# nautilus-board.net
KiCad netlist of a schematic drawn in EAGLE
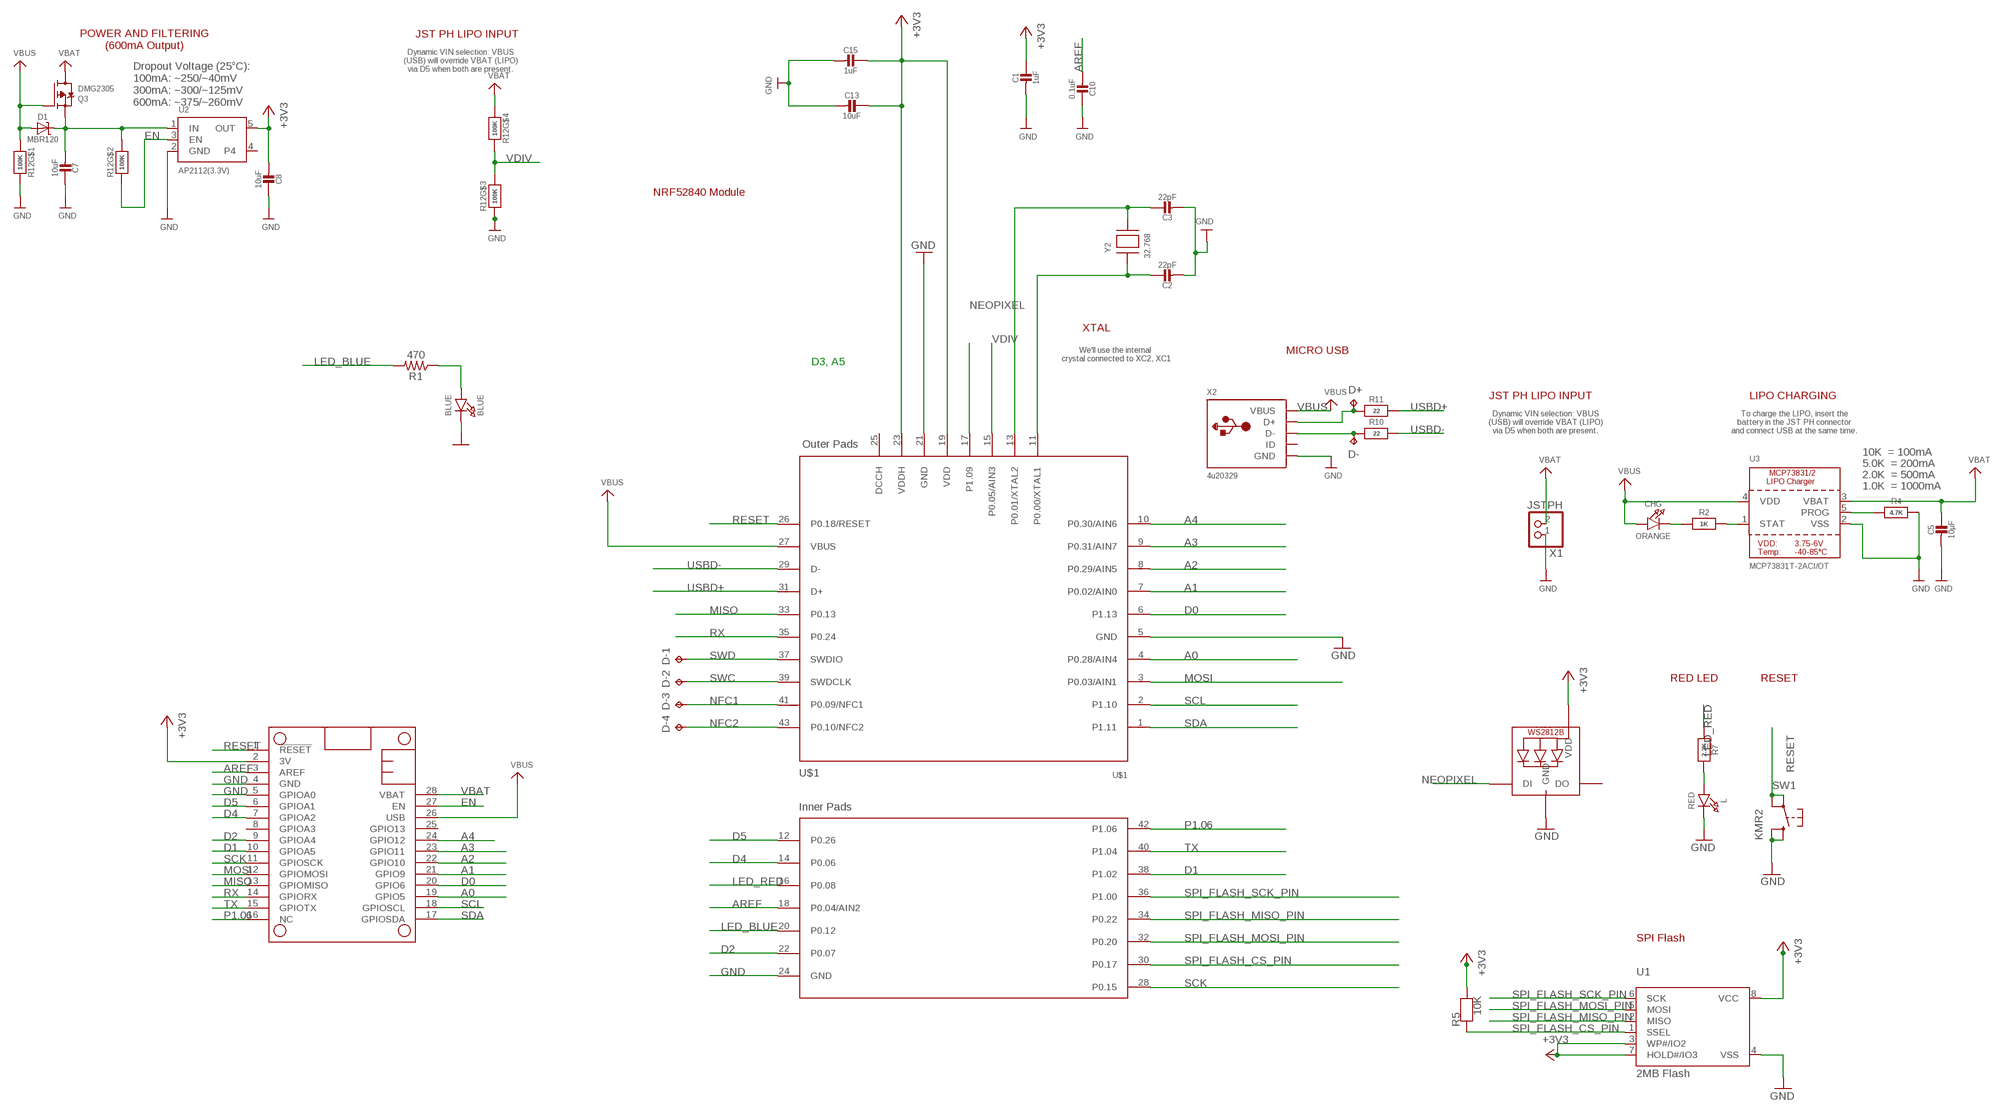
[diagram p0: schematic, sheet 1]

(export (version "E")
  (design (tool "Eeschema 10.0.6"))
  (components
    (comp (ref "BLUE")
      (value "BLUE")
      (footprint "eagle-import:CHIPLED_0805_NOOUTLINE")
      (libsource (lib "eagle-import") (part "LED0805_NOOUTLINE"))
    )
    (comp (ref "C1")
      (value "1uF")
      (footprint "eagle-import:0603-NO")
      (libsource (lib "eagle-import") (part "CAP_CERAMIC0603_NO"))
    )
    (comp (ref "C2")
      (value "22pF")
      (footprint "eagle-import:0603-NO")
      (libsource (lib "eagle-import") (part "CAP_CERAMIC0603_NO"))
    )
    (comp (ref "C3")
      (value "22pF")
      (footprint "eagle-import:0603-NO")
      (libsource (lib "eagle-import") (part "CAP_CERAMIC0603_NO"))
    )
    (comp (ref "C5")
      (value "10µF")
      (footprint "eagle-import:0805-NO")
      (libsource (lib "eagle-import") (part "CAP_CERAMIC0805-NOOUTLINE"))
    )
    (comp (ref "C7")
      (value "10uF")
      (footprint "eagle-import:0805-NO")
      (libsource (lib "eagle-import") (part "CAP_CERAMIC0805-NOOUTLINE"))
    )
    (comp (ref "C8")
      (value "10uF")
      (footprint "eagle-import:0805-NO")
      (libsource (lib "eagle-import") (part "CAP_CERAMIC0805-NOOUTLINE"))
    )
    (comp (ref "C10")
      (value "0.1uF")
      (footprint "eagle-import:0603-NO")
      (libsource (lib "eagle-import") (part "CAP_CERAMIC0603_NO"))
    )
    (comp (ref "C13")
      (value "10uF")
      (footprint "eagle-import:0805-NO")
      (libsource (lib "eagle-import") (part "CAP_CERAMIC0805-NOOUTLINE"))
    )
    (comp (ref "C15")
      (value "1uF")
      (footprint "eagle-import:0603-NO")
      (libsource (lib "eagle-import") (part "CAP_CERAMIC0603_NO"))
    )
    (comp (ref "CHG")
      (value "ORANGE")
      (footprint "eagle-import:CHIPLED_0805_NOOUTLINE")
      (libsource (lib "eagle-import") (part "LED0805_NOOUTLINE"))
    )
    (comp (ref "D+")
      (value "TPTP10R")
      (footprint "eagle-import:TP10R")
      (libsource (lib "eagle-import") (part "TPTP10R"))
    )
    (comp (ref "D-")
      (value "TPTP10R")
      (footprint "eagle-import:TP10R")
      (libsource (lib "eagle-import") (part "TPTP10R"))
    )
    (comp (ref "D-1")
      (value "TPB1,27")
      (footprint "eagle-import:B1,27")
      (libsource (lib "eagle-import") (part "TPB1,27"))
    )
    (comp (ref "D-2")
      (value "TPB1,27")
      (footprint "eagle-import:B1,27")
      (libsource (lib "eagle-import") (part "TPB1,27"))
    )
    (comp (ref "D-3")
      (value "TPB1,27")
      (footprint "eagle-import:B1,27")
      (libsource (lib "eagle-import") (part "TPB1,27"))
    )
    (comp (ref "D-4")
      (value "TPB1,27")
      (footprint "eagle-import:B1,27")
      (libsource (lib "eagle-import") (part "TPB1,27"))
    )
    (comp (ref "D1")
      (value "MBR120")
      (footprint "eagle-import:SOD-123")
      (libsource (lib "eagle-import") (part "DIODE-SCHOTTKYSOD-123"))
    )
    (comp (ref "L")
      (value "RED")
      (footprint "eagle-import:CHIPLED_0805_NOOUTLINE")
      (libsource (lib "eagle-import") (part "LED0805_NOOUTLINE"))
    )
    (comp (ref "LED1")
      (value "WS2812B3535")
      (footprint "eagle-import:LED3535")
      (libsource (lib "eagle-import") (part "WS2812B3535"))
    )
    (comp (ref "MS1")
      (value "FEATHERWING")
      (footprint "eagle-import:FEATHERWING")
      (libsource (lib "eagle-import") (part "FEATHERWING"))
    )
    (comp (ref "Q3")
      (value "DMG2305")
      (footprint "eagle-import:SOT23-R")
      (libsource (lib "eagle-import") (part "MOSFET-P"))
    )
    (comp (ref "R1")
      (value "470")
      (footprint "eagle-import:0603")
      (libsource (lib "eagle-import") (part "470OHM-0603-1/10W-1%"))
    )
    (comp (ref "R2")
      (value "1K")
      (footprint "eagle-import:0603-NO")
      (libsource (lib "eagle-import") (part "RESISTOR_0603_NOOUT"))
    )
    (comp (ref "R4")
      (value "4.7K")
      (footprint "eagle-import:0603-NO")
      (libsource (lib "eagle-import") (part "RESISTOR_0603_NOOUT"))
    )
    (comp (ref "R5")
      (value "10K")
      (footprint "eagle-import:0603-NO")
      (libsource (lib "eagle-import") (part "RESISTOR_0603_NOOUT"))
    )
    (comp (ref "R7")
      (value "2.2K")
      (footprint "eagle-import:0603-NO")
      (libsource (lib "eagle-import") (part "RESISTOR_0603_NOOUT"))
    )
    (comp (ref "R10")
      (value "22")
      (footprint "eagle-import:0603-NO")
      (libsource (lib "eagle-import") (part "RESISTOR_0603_NOOUT"))
    )
    (comp (ref "R11")
      (value "22")
      (footprint "eagle-import:0603-NO")
      (libsource (lib "eagle-import") (part "RESISTOR_0603_NOOUT"))
    )
    (comp (ref "R12")
      (value "100K")
      (footprint "eagle-import:RESPACK_4X0603")
      (libsource (lib "eagle-import") (part "RESISTOR_4PACK"))
    )
    (comp (ref "SW1")
      (value "KMR2")
      (footprint "eagle-import:BTN_KMR2_4.6X2.8")
      (libsource (lib "eagle-import") (part "SWITCH_TACT_SMT4.6X2.8"))
    )
    (comp (ref "U$1")
      (value "E73-2G4M08S1C")
      (footprint "eagle-import:PE73(2G4M08S1C)")
      (libsource (lib "eagle-import") (part "E73-2G4M08S1C"))
    )
    (comp (ref "U1")
      (value "2MB Flash")
      (footprint "eagle-import:SOIC8_208MIL")
      (libsource (lib "eagle-import") (part "SPIFLASH_SOIC8208MIL"))
    )
    (comp (ref "U2")
      (value "AP2112(3.3V)")
      (footprint "eagle-import:SOT23-5")
      (libsource (lib "eagle-import") (part "VREG_SOT23-5"))
    )
    (comp (ref "U3")
      (value "MCP73831T-2ACI/OT")
      (footprint "eagle-import:SOT23-5")
      (libsource (lib "eagle-import") (part "MCP73831/2"))
    )
    (comp (ref "X1")
      (value "JSTPH")
      (footprint "eagle-import:JSTPH2")
      (libsource (lib "eagle-import") (part "CON_JST_PH_2PIN"))
    )
    (comp (ref "X2")
      (value "4u20329")
      (footprint "eagle-import:4UCONN_20329_V2")
      (libsource (lib "eagle-import") (part "USB_MICRO_20329_V2"))
    )
    (comp (ref "Y2")
      (value "32.768")
      (footprint "eagle-import:XTAL3215")
      (libsource (lib "eagle-import") (part "XTAL-3.2X1.5"))
    )
  )
  (nets
    (net (code "1") (name "+3V3") (class "Default")
      (node (ref "C1") (pin "1") (pinfunction "1_1") (pintype "passive"))
      (node (ref "C13") (pin "1") (pinfunction "1_1") (pintype "passive"))
      (node (ref "C15") (pin "1") (pinfunction "1_1") (pintype "passive"))
      (node (ref "C8") (pin "2") (pinfunction "2_2") (pintype "passive"))
      (node (ref "LED1") (pin "2") (pinfunction "VDD_2") (pintype "power_in"))
      (node (ref "MS1") (pin "2") (pinfunction "3V_2") (pintype "power_in"))
      (node (ref "R5") (pin "2") (pinfunction "2_2") (pintype "passive"))
      (node (ref "U$1") (pin "19") (pinfunction "VDD_19") (pintype "power_in"))
      (node (ref "U$1") (pin "23") (pinfunction "VDDH_23") (pintype "bidirectional"))
      (node (ref "U1") (pin "3") (pinfunction "WP#/IO2_3") (pintype "bidirectional"))
      (node (ref "U1") (pin "7") (pinfunction "HOLD#/IO3_7") (pintype "bidirectional"))
      (node (ref "U1") (pin "8") (pinfunction "VCC_8") (pintype "bidirectional"))
      (node (ref "U2") (pin "5") (pinfunction "OUT_5") (pintype "power_in"))
    )
    (net (code "2") (name "/A0") (class "Default")
      (node (ref "MS1") (pin "19") (pinfunction "GPIO5_19") (pintype "bidirectional"))
      (node (ref "U$1") (pin "4") (pinfunction "P0.28/AIN4_4") (pintype "bidirectional"))
    )
    (net (code "3") (name "/A1") (class "Default")
      (node (ref "MS1") (pin "21") (pinfunction "GPIO9_21") (pintype "bidirectional"))
      (node (ref "U$1") (pin "7") (pinfunction "P0.02/AIN0_7") (pintype "bidirectional"))
    )
    (net (code "4") (name "/A2") (class "Default")
      (node (ref "MS1") (pin "22") (pinfunction "GPIO10_22") (pintype "bidirectional"))
      (node (ref "U$1") (pin "8") (pinfunction "P0.29/AIN5_8") (pintype "bidirectional"))
    )
    (net (code "5") (name "/A3") (class "Default")
      (node (ref "MS1") (pin "23") (pinfunction "GPIO11_23") (pintype "bidirectional"))
      (node (ref "U$1") (pin "9") (pinfunction "P0.31/AIN7_9") (pintype "bidirectional"))
    )
    (net (code "6") (name "/A4") (class "Default")
      (node (ref "MS1") (pin "24") (pinfunction "GPIO12_24") (pintype "bidirectional"))
      (node (ref "U$1") (pin "10") (pinfunction "P0.30/AIN6_10") (pintype "bidirectional"))
    )
    (net (code "7") (name "/AREF") (class "Default")
      (node (ref "C10") (pin "2") (pinfunction "2_2") (pintype "passive"))
      (node (ref "MS1") (pin "3") (pinfunction "AREF_3") (pintype "passive"))
      (node (ref "U$1") (pin "18") (pinfunction "P0.04/AIN2_18") (pintype "bidirectional"))
    )
    (net (code "8") (name "/D0") (class "Default")
      (node (ref "MS1") (pin "20") (pinfunction "GPIO6_20") (pintype "bidirectional"))
      (node (ref "U$1") (pin "6") (pinfunction "P1.13_6") (pintype "bidirectional"))
    )
    (net (code "9") (name "/D1") (class "Default")
      (node (ref "MS1") (pin "10") (pinfunction "GPIOA5_10") (pintype "bidirectional"))
      (node (ref "U$1") (pin "38") (pinfunction "P1.02_38") (pintype "bidirectional"))
    )
    (net (code "10") (name "/D2") (class "Default")
      (node (ref "MS1") (pin "9") (pinfunction "GPIOA4_9") (pintype "bidirectional"))
      (node (ref "U$1") (pin "22") (pinfunction "P0.07_22") (pintype "bidirectional"))
    )
    (net (code "11") (name "/D4") (class "Default")
      (node (ref "MS1") (pin "7") (pinfunction "GPIOA2_7") (pintype "bidirectional"))
      (node (ref "U$1") (pin "14") (pinfunction "P0.06_14") (pintype "bidirectional"))
    )
    (net (code "12") (name "/D5") (class "Default")
      (node (ref "MS1") (pin "6") (pinfunction "GPIOA1_6") (pintype "bidirectional"))
      (node (ref "U$1") (pin "12") (pinfunction "P0.26_12") (pintype "bidirectional"))
    )
    (net (code "13") (name "/EN") (class "Default")
      (node (ref "MS1") (pin "27") (pinfunction "EN_27") (pintype "passive"))
      (node (ref "R12") (pin "2") (pinfunction "1_2") (pintype "passive"))
      (node (ref "U2") (pin "3") (pinfunction "EN_3") (pintype "input"))
    )
    (net (code "14") (name "/LED_BLUE") (class "Default")
      (node (ref "R1") (pin "2") (pinfunction "2_2") (pintype "passive"))
      (node (ref "U$1") (pin "20") (pinfunction "P0.12_20") (pintype "bidirectional"))
    )
    (net (code "15") (name "/LED_RED") (class "Default")
      (node (ref "R7") (pin "1") (pinfunction "1_1") (pintype "passive"))
      (node (ref "U$1") (pin "16") (pinfunction "P0.08_16") (pintype "bidirectional"))
    )
    (net (code "16") (name "/MISO") (class "Default")
      (node (ref "MS1") (pin "13") (pinfunction "GPIOMISO_13") (pintype "bidirectional"))
      (node (ref "U$1") (pin "33") (pinfunction "P0.13_33") (pintype "bidirectional"))
    )
    (net (code "17") (name "/MOSI") (class "Default")
      (node (ref "MS1") (pin "12") (pinfunction "GPIOMOSI_12") (pintype "bidirectional"))
      (node (ref "U$1") (pin "3") (pinfunction "P0.03/AIN1_3") (pintype "bidirectional"))
    )
    (net (code "18") (name "/NEOPIXEL") (class "Default")
      (node (ref "LED1") (pin "1") (pinfunction "DI_1") (pintype "input"))
      (node (ref "U$1") (pin "17") (pinfunction "P1.09_17") (pintype "bidirectional"))
    )
    (net (code "19") (name "/NFC1") (class "Default")
      (node (ref "D-3") (pin "TP") (pinfunction "TP_TP") (pintype "input"))
      (node (ref "U$1") (pin "41") (pinfunction "P0.09/NFC1_41") (pintype "bidirectional"))
    )
    (net (code "20") (name "/NFC2") (class "Default")
      (node (ref "D-4") (pin "TP") (pinfunction "TP_TP") (pintype "input"))
      (node (ref "U$1") (pin "43") (pinfunction "P0.10/NFC2_43") (pintype "bidirectional"))
    )
    (net (code "21") (name "/P1.06") (class "Default")
      (node (ref "MS1") (pin "16") (pinfunction "NC_16") (pintype "passive"))
      (node (ref "U$1") (pin "42") (pinfunction "P1.06_42") (pintype "bidirectional"))
    )
    (net (code "22") (name "/RESET") (class "Default")
      (node (ref "MS1") (pin "1") (pinfunction "~{RESET}_1") (pintype "input"))
      (node (ref "SW1") (pin "A") (pinfunction "P_A") (pintype "passive"))
      (node (ref "SW1") (pin "A'") (pinfunction "P1_A'") (pintype "passive"))
      (node (ref "U$1") (pin "26") (pinfunction "P0.18/RESET_26") (pintype "bidirectional"))
    )
    (net (code "23") (name "/RX") (class "Default")
      (node (ref "MS1") (pin "14") (pinfunction "GPIORX_14") (pintype "bidirectional"))
      (node (ref "U$1") (pin "35") (pinfunction "P0.24_35") (pintype "bidirectional"))
    )
    (net (code "24") (name "/SCK") (class "Default")
      (node (ref "MS1") (pin "11") (pinfunction "GPIOSCK_11") (pintype "bidirectional"))
      (node (ref "U$1") (pin "28") (pinfunction "P0.15_28") (pintype "bidirectional"))
    )
    (net (code "25") (name "/SCL") (class "Default")
      (node (ref "MS1") (pin "18") (pinfunction "GPIOSCL_18") (pintype "bidirectional"))
      (node (ref "U$1") (pin "2") (pinfunction "P1.10_2") (pintype "bidirectional"))
    )
    (net (code "26") (name "/SDA") (class "Default")
      (node (ref "MS1") (pin "17") (pinfunction "GPIOSDA_17") (pintype "bidirectional"))
      (node (ref "U$1") (pin "1") (pinfunction "P1.11_1") (pintype "bidirectional"))
    )
    (net (code "27") (name "/SPI_FLASH_CS_PIN") (class "Default")
      (node (ref "R5") (pin "1") (pinfunction "1_1") (pintype "passive"))
      (node (ref "U$1") (pin "30") (pinfunction "P0.17_30") (pintype "bidirectional"))
      (node (ref "U1") (pin "1") (pinfunction "SSEL_1") (pintype "bidirectional"))
    )
    (net (code "28") (name "/SPI_FLASH_MISO_PIN") (class "Default")
      (node (ref "U$1") (pin "34") (pinfunction "P0.22_34") (pintype "bidirectional"))
      (node (ref "U1") (pin "2") (pinfunction "MISO_2") (pintype "bidirectional"))
    )
    (net (code "29") (name "/SPI_FLASH_MOSI_PIN") (class "Default")
      (node (ref "U$1") (pin "32") (pinfunction "P0.20_32") (pintype "input"))
      (node (ref "U1") (pin "5") (pinfunction "MOSI_5") (pintype "bidirectional"))
    )
    (net (code "30") (name "/SPI_FLASH_SCK_PIN") (class "Default")
      (node (ref "U$1") (pin "36") (pinfunction "P1.00_36") (pintype "bidirectional"))
      (node (ref "U1") (pin "6") (pinfunction "SCK_6") (pintype "bidirectional"))
    )
    (net (code "31") (name "/SWC") (class "Default")
      (node (ref "D-2") (pin "TP") (pinfunction "TP_TP") (pintype "input"))
      (node (ref "U$1") (pin "39") (pinfunction "SWDCLK_39") (pintype "bidirectional"))
    )
    (net (code "32") (name "/SWD") (class "Default")
      (node (ref "D-1") (pin "TP") (pinfunction "TP_TP") (pintype "input"))
      (node (ref "U$1") (pin "37") (pinfunction "SWDIO_37") (pintype "bidirectional"))
    )
    (net (code "33") (name "/TX") (class "Default")
      (node (ref "MS1") (pin "15") (pinfunction "GPIOTX_15") (pintype "bidirectional"))
      (node (ref "U$1") (pin "40") (pinfunction "P1.04_40") (pintype "bidirectional"))
    )
    (net (code "34") (name "/USBD+") (class "Default")
      (node (ref "R11") (pin "2") (pinfunction "2_2") (pintype "passive"))
      (node (ref "U$1") (pin "31") (pinfunction "D+_31") (pintype "bidirectional"))
    )
    (net (code "35") (name "/USBD-") (class "Default")
      (node (ref "R10") (pin "2") (pinfunction "2_2") (pintype "passive"))
      (node (ref "U$1") (pin "29") (pinfunction "D-_29") (pintype "bidirectional"))
    )
    (net (code "36") (name "/VDIV") (class "Default")
      (node (ref "R12") (pin "5") (pinfunction "2_5") (pintype "passive"))
      (node (ref "R12") (pin "6") (pinfunction "2_6") (pintype "passive"))
      (node (ref "U$1") (pin "15") (pinfunction "P0.05/AIN3_15") (pintype "bidirectional"))
    )
    (net (code "37") (name "GND") (class "Default")
      (node (ref "BLUE") (pin "C") (pinfunction "C_C") (pintype "passive"))
      (node (ref "C1") (pin "2") (pinfunction "2_2") (pintype "passive"))
      (node (ref "C10") (pin "1") (pinfunction "1_1") (pintype "passive"))
      (node (ref "C13") (pin "2") (pinfunction "2_2") (pintype "passive"))
      (node (ref "C15") (pin "2") (pinfunction "2_2") (pintype "passive"))
      (node (ref "C2") (pin "2") (pinfunction "2_2") (pintype "passive"))
      (node (ref "C3") (pin "2") (pinfunction "2_2") (pintype "passive"))
      (node (ref "C5") (pin "2") (pinfunction "2_2") (pintype "passive"))
      (node (ref "C7") (pin "1") (pinfunction "1_1") (pintype "passive"))
      (node (ref "C8") (pin "1") (pinfunction "1_1") (pintype "passive"))
      (node (ref "L") (pin "C") (pinfunction "C_C") (pintype "passive"))
      (node (ref "LED1") (pin "4") (pinfunction "GND_4") (pintype "power_in"))
      (node (ref "MS1") (pin "4") (pinfunction "GND_4") (pintype "power_in"))
      (node (ref "MS1") (pin "5") (pinfunction "GPIOA0_5") (pintype "bidirectional"))
      (node (ref "R12") (pin "3") (pinfunction "1_3") (pintype "passive"))
      (node (ref "R12") (pin "8") (pinfunction "2_8") (pintype "passive"))
      (node (ref "R4") (pin "2") (pinfunction "2_2") (pintype "passive"))
      (node (ref "SW1") (pin "B") (pinfunction "S_B") (pintype "passive"))
      (node (ref "SW1") (pin "B'") (pinfunction "S1_B'") (pintype "passive"))
      (node (ref "U$1") (pin "21") (pinfunction "GND_21") (pintype "bidirectional"))
      (node (ref "U$1") (pin "24") (pinfunction "GND_24") (pintype "bidirectional"))
      (node (ref "U$1") (pin "5") (pinfunction "GND_5") (pintype "power_in"))
      (node (ref "U1") (pin "4") (pinfunction "VSS_4") (pintype "bidirectional"))
      (node (ref "U2") (pin "2") (pinfunction "GND_2") (pintype "power_in"))
      (node (ref "U3") (pin "2") (pinfunction "VSS_2") (pintype "power_in"))
      (node (ref "X1") (pin "1") (pinfunction "1_1") (pintype "passive"))
      (node (ref "X2") (pin "BASE@1") (pinfunction "GND_BASE@1") (pintype "power_in"))
      (node (ref "X2") (pin "BASE@2") (pinfunction "GND_BASE@2") (pintype "power_in"))
      (node (ref "X2") (pin "GND") (pinfunction "GND_GND") (pintype "power_in"))
      (node (ref "X2") (pin "SPRT@1") (pinfunction "GND_SPRT@1") (pintype "power_in"))
      (node (ref "X2") (pin "SPRT@2") (pinfunction "GND_SPRT@2") (pintype "power_in"))
      (node (ref "X2") (pin "SPRT@3") (pinfunction "GND_SPRT@3") (pintype "power_in"))
      (node (ref "X2") (pin "SPRT@4") (pinfunction "GND_SPRT@4") (pintype "power_in"))
    )
    (net (code "38") (name "Net-(BLUE-PadA)") (class "Default")
      (node (ref "BLUE") (pin "A") (pinfunction "A_A") (pintype "passive"))
      (node (ref "R1") (pin "1") (pinfunction "1_1") (pintype "passive"))
    )
    (net (code "39") (name "Net-(CHG-PadC)") (class "Default")
      (node (ref "CHG") (pin "C") (pinfunction "C_C") (pintype "passive"))
      (node (ref "R2") (pin "1") (pinfunction "1_1") (pintype "passive"))
    )
    (net (code "40") (name "Net-(D+-PadTP)") (class "Default")
      (node (ref "D+") (pin "TP") (pinfunction "TP_TP") (pintype "input"))
      (node (ref "R11") (pin "1") (pinfunction "1_1") (pintype "passive"))
      (node (ref "X2") (pin "D+") (pinfunction "D+_D+") (pintype "bidirectional"))
    )
    (net (code "41") (name "Net-(D--PadTP)") (class "Default")
      (node (ref "D-") (pin "TP") (pinfunction "TP_TP") (pintype "input"))
      (node (ref "R10") (pin "1") (pinfunction "1_1") (pintype "passive"))
      (node (ref "X2") (pin "D-") (pinfunction "D-_D-") (pintype "bidirectional"))
    )
    (net (code "42") (name "Net-(L-PadA)") (class "Default")
      (node (ref "L") (pin "A") (pinfunction "A_A") (pintype "passive"))
      (node (ref "R7") (pin "2") (pinfunction "2_2") (pintype "passive"))
    )
    (net (code "43") (name "Net-(Q3-S)") (class "Default")
      (node (ref "C7") (pin "2") (pinfunction "2_2") (pintype "passive"))
      (node (ref "D1") (pin "C") (pinfunction "C_C") (pintype "passive"))
      (node (ref "Q3") (pin "2") (pinfunction "S_2") (pintype "passive"))
      (node (ref "R12") (pin "7") (pinfunction "2_7") (pintype "passive"))
      (node (ref "U2") (pin "1") (pinfunction "IN_1") (pintype "power_in"))
    )
    (net (code "44") (name "Net-(U$1-P0.00{slash}XTAL1)") (class "Default")
      (node (ref "C2") (pin "1") (pinfunction "1_1") (pintype "passive"))
      (node (ref "U$1") (pin "11") (pinfunction "P0.00/XTAL1_11") (pintype "passive"))
      (node (ref "Y2") (pin "P$1") (pinfunction "P$1_P$1") (pintype "bidirectional"))
    )
    (net (code "45") (name "Net-(U$1-P0.01{slash}XTAL2)") (class "Default")
      (node (ref "C3") (pin "1") (pinfunction "1_1") (pintype "passive"))
      (node (ref "U$1") (pin "13") (pinfunction "P0.01/XTAL2_13") (pintype "power_in"))
      (node (ref "Y2") (pin "P$2") (pinfunction "P$2_P$2") (pintype "bidirectional"))
    )
    (net (code "46") (name "Net-(U3-PROG)") (class "Default")
      (node (ref "R4") (pin "1") (pinfunction "1_1") (pintype "passive"))
      (node (ref "U3") (pin "5") (pinfunction "PROG_5") (pintype "input"))
    )
    (net (code "47") (name "Net-(U3-STAT)") (class "Default")
      (node (ref "R2") (pin "2") (pinfunction "2_2") (pintype "passive"))
      (node (ref "U3") (pin "1") (pinfunction "STAT_1") (pintype "output"))
    )
    (net (code "48") (name "VBAT") (class "Default")
      (node (ref "C5") (pin "1") (pinfunction "1_1") (pintype "passive"))
      (node (ref "MS1") (pin "28") (pinfunction "VBAT_28") (pintype "power_in"))
      (node (ref "Q3") (pin "3") (pinfunction "D_3") (pintype "passive"))
      (node (ref "R12") (pin "4") (pinfunction "1_4") (pintype "passive"))
      (node (ref "U3") (pin "3") (pinfunction "VBAT_3") (pintype "power_in"))
      (node (ref "X1") (pin "2") (pinfunction "2_2") (pintype "passive"))
    )
    (net (code "49") (name "VBUS") (class "Default")
      (node (ref "CHG") (pin "A") (pinfunction "A_A") (pintype "passive"))
      (node (ref "D1") (pin "A") (pinfunction "A_A") (pintype "passive"))
      (node (ref "MS1") (pin "26") (pinfunction "USB_26") (pintype "power_in"))
      (node (ref "Q3") (pin "1") (pinfunction "G_1") (pintype "passive"))
      (node (ref "R12") (pin "1") (pinfunction "1_1") (pintype "passive"))
      (node (ref "U$1") (pin "27") (pinfunction "VBUS_27") (pintype "power_in"))
      (node (ref "U3") (pin "4") (pinfunction "VDD_4") (pintype "power_in"))
      (node (ref "X2") (pin "VBUS") (pinfunction "VBUS_VBUS") (pintype "power_in"))
    )
    (net (code "50") (name "unconnected-(LED1-DO-Pad3)") (class "Default")
      (node (ref "LED1") (pin "3") (pinfunction "DO_3") (pintype "output"))
    )
    (net (code "51") (name "unconnected-(MS1-GPIO13-Pad25)") (class "Default")
      (node (ref "MS1") (pin "25") (pinfunction "GPIO13_25") (pintype "bidirectional"))
    )
    (net (code "52") (name "unconnected-(MS1-GPIOA3-Pad8)") (class "Default")
      (node (ref "MS1") (pin "8") (pinfunction "GPIOA3_8") (pintype "bidirectional"))
    )
    (net (code "53") (name "unconnected-(U$1-DCCH-Pad25)") (class "Default")
      (node (ref "U$1") (pin "25") (pinfunction "DCCH_25") (pintype "bidirectional"))
    )
    (net (code "54") (name "unconnected-(U2-P4-Pad4)") (class "Default")
      (node (ref "U2") (pin "4") (pinfunction "P4_4") (pintype "bidirectional"))
    )
    (net (code "55") (name "unconnected-(X2-PadID)") (class "Default")
      (node (ref "X2") (pin "ID") (pinfunction "ID_ID") (pintype "bidirectional"))
    )
  )
)
